# LilyPad_White_5pcs_v02.net
KiCad netlist of a schematic drawn in EAGLE
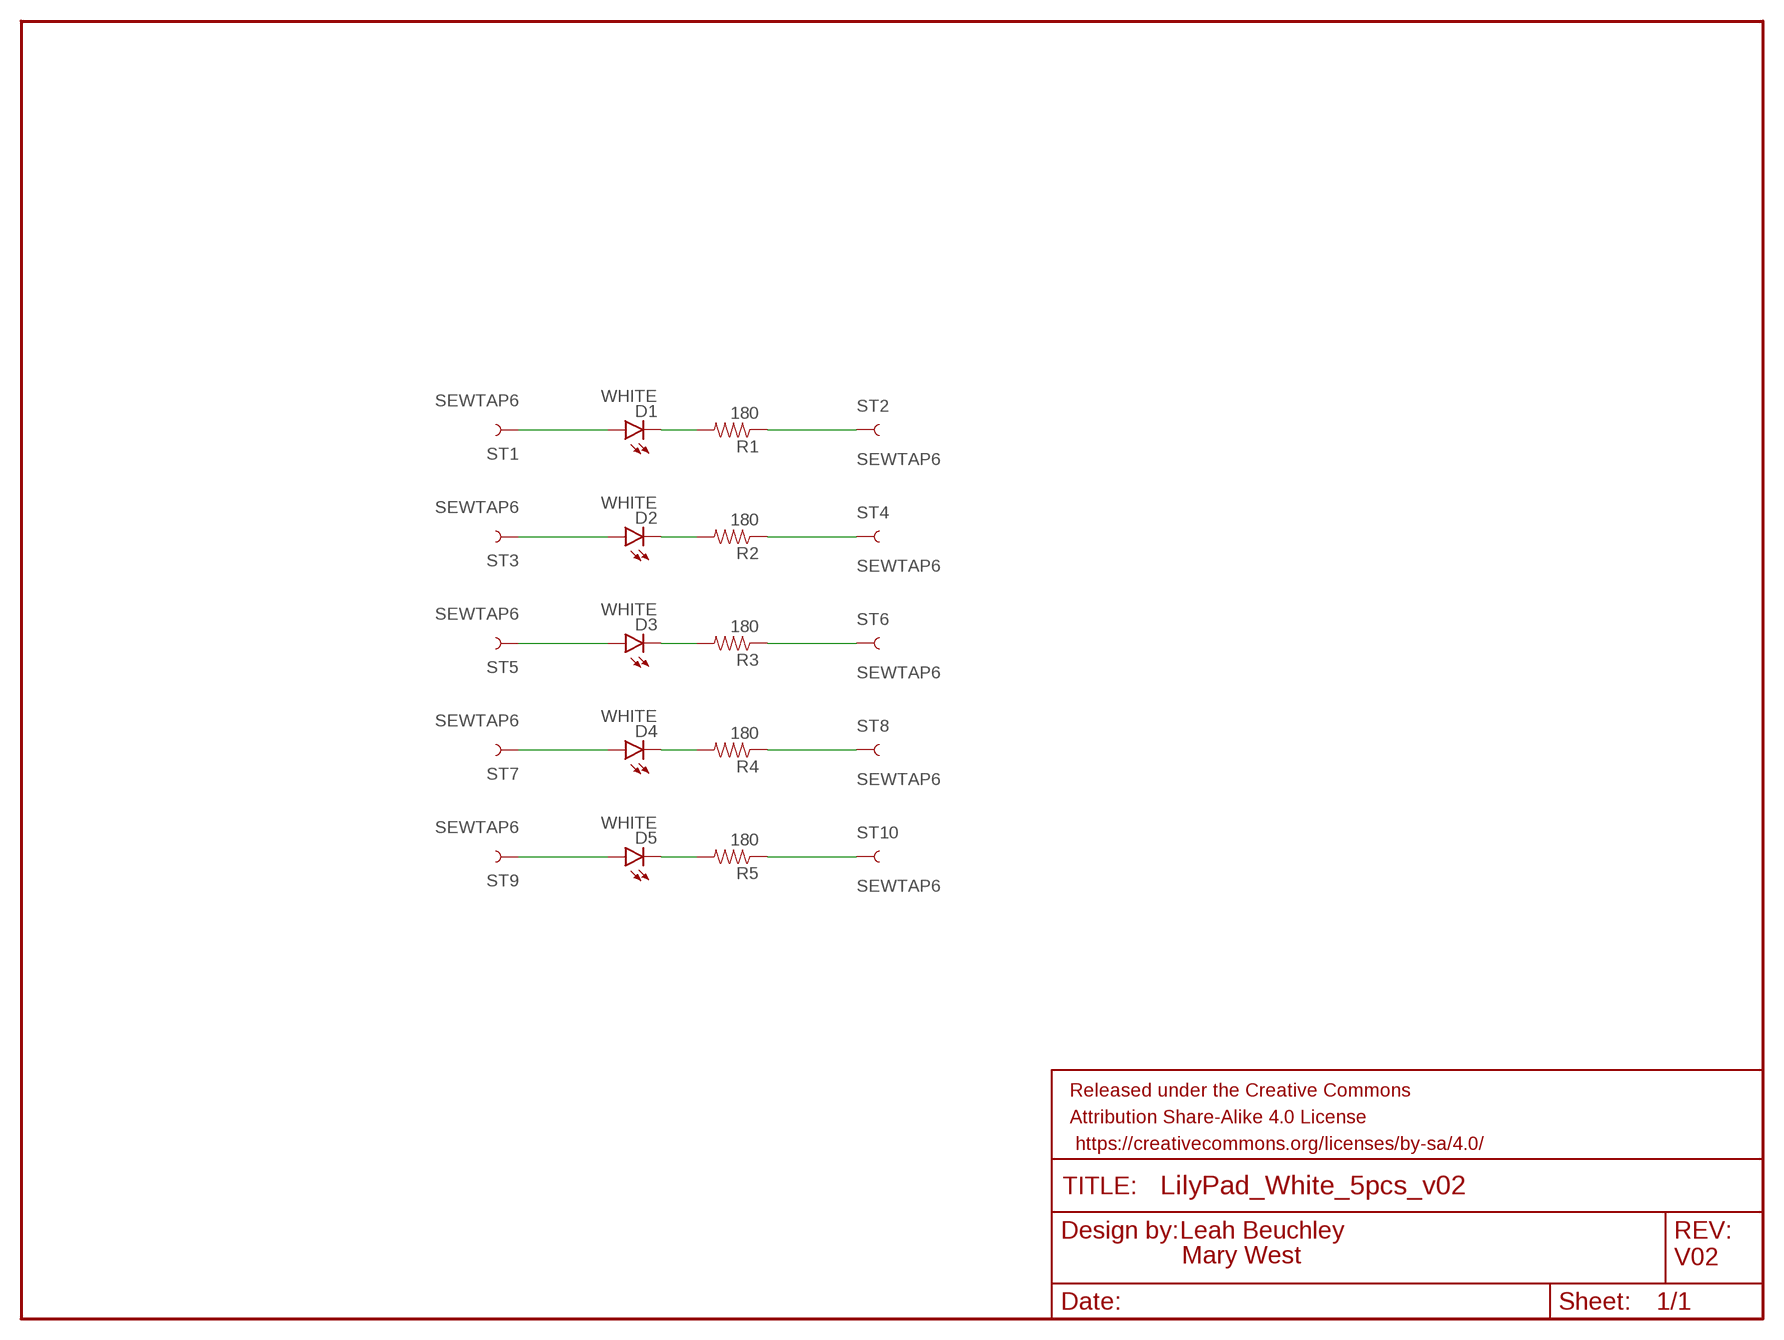
[diagram p0: schematic, sheet 1]

(export (version "E")
  (design (tool "Eeschema 10.0.6"))
  (components
    (comp (ref "D1")
      (value "WHITE")
      (footprint "eagle-import:LED-1206")
      (libsource (lib "eagle-import") (part "LED-WHITE1206"))
    )
    (comp (ref "D2")
      (value "WHITE")
      (footprint "eagle-import:LED-1206")
      (libsource (lib "eagle-import") (part "LED-WHITE1206"))
    )
    (comp (ref "D3")
      (value "WHITE")
      (footprint "eagle-import:LED-1206")
      (libsource (lib "eagle-import") (part "LED-WHITE1206"))
    )
    (comp (ref "D4")
      (value "WHITE")
      (footprint "eagle-import:LED-1206")
      (libsource (lib "eagle-import") (part "LED-WHITE1206"))
    )
    (comp (ref "D5")
      (value "WHITE")
      (footprint "eagle-import:LED-1206")
      (libsource (lib "eagle-import") (part "LED-WHITE1206"))
    )
    (comp (ref "FRAME1")
      (value "FRAME-LETTER")
      (footprint "eagle-import:CREATIVE_COMMONS")
      (libsource (lib "eagle-import") (part "FRAME-LETTER"))
    )
    (comp (ref "R1")
      (value "180")
      (footprint "eagle-import:0603-RES")
      (libsource (lib "eagle-import") (part "180OHM1/10W1%(0603)"))
    )
    (comp (ref "R2")
      (value "180")
      (footprint "eagle-import:0603-RES")
      (libsource (lib "eagle-import") (part "180OHM1/10W1%(0603)"))
    )
    (comp (ref "R3")
      (value "180")
      (footprint "eagle-import:0603-RES")
      (libsource (lib "eagle-import") (part "180OHM1/10W1%(0603)"))
    )
    (comp (ref "R4")
      (value "180")
      (footprint "eagle-import:0603-RES")
      (libsource (lib "eagle-import") (part "180OHM1/10W1%(0603)"))
    )
    (comp (ref "R5")
      (value "180")
      (footprint "eagle-import:0603-RES")
      (libsource (lib "eagle-import") (part "180OHM1/10W1%(0603)"))
    )
    (comp (ref "ST1")
      (value "SEWTAP6")
      (footprint "eagle-import:PETAL-SMALL-2SIDE")
      (libsource (lib "eagle-import") (part "SEWTAP6"))
    )
    (comp (ref "ST2")
      (value "SEWTAP6")
      (footprint "eagle-import:PETAL-SMALL-2SIDE")
      (libsource (lib "eagle-import") (part "SEWTAP6"))
    )
    (comp (ref "ST3")
      (value "SEWTAP6")
      (footprint "eagle-import:PETAL-SMALL-2SIDE")
      (libsource (lib "eagle-import") (part "SEWTAP6"))
    )
    (comp (ref "ST4")
      (value "SEWTAP6")
      (footprint "eagle-import:PETAL-SMALL-2SIDE")
      (libsource (lib "eagle-import") (part "SEWTAP6"))
    )
    (comp (ref "ST5")
      (value "SEWTAP6")
      (footprint "eagle-import:PETAL-SMALL-2SIDE")
      (libsource (lib "eagle-import") (part "SEWTAP6"))
    )
    (comp (ref "ST6")
      (value "SEWTAP6")
      (footprint "eagle-import:PETAL-SMALL-2SIDE")
      (libsource (lib "eagle-import") (part "SEWTAP6"))
    )
    (comp (ref "ST7")
      (value "SEWTAP6")
      (footprint "eagle-import:PETAL-SMALL-2SIDE")
      (libsource (lib "eagle-import") (part "SEWTAP6"))
    )
    (comp (ref "ST8")
      (value "SEWTAP6")
      (footprint "eagle-import:PETAL-SMALL-2SIDE")
      (libsource (lib "eagle-import") (part "SEWTAP6"))
    )
    (comp (ref "ST9")
      (value "SEWTAP6")
      (footprint "eagle-import:PETAL-SMALL-2SIDE")
      (libsource (lib "eagle-import") (part "SEWTAP6"))
    )
    (comp (ref "ST10")
      (value "SEWTAP6")
      (footprint "eagle-import:PETAL-SMALL-2SIDE")
      (libsource (lib "eagle-import") (part "SEWTAP6"))
    )
  )
  (nets
    (net (code "1") (name "Net-(D1-PadA)") (class "Default")
      (node (ref "D1") (pin "A") (pinfunction "A_A") (pintype "passive"))
      (node (ref "ST1") (pin "1") (pinfunction "1_1") (pintype "bidirectional"))
    )
    (net (code "2") (name "Net-(D1-PadC)") (class "Default")
      (node (ref "D1") (pin "C") (pinfunction "C_C") (pintype "passive"))
      (node (ref "R1") (pin "2") (pinfunction "2_2") (pintype "passive"))
    )
    (net (code "3") (name "Net-(D2-PadA)") (class "Default")
      (node (ref "D2") (pin "A") (pinfunction "A_A") (pintype "passive"))
      (node (ref "ST3") (pin "1") (pinfunction "1_1") (pintype "bidirectional"))
    )
    (net (code "4") (name "Net-(D2-PadC)") (class "Default")
      (node (ref "D2") (pin "C") (pinfunction "C_C") (pintype "passive"))
      (node (ref "R2") (pin "2") (pinfunction "2_2") (pintype "passive"))
    )
    (net (code "5") (name "Net-(D3-PadA)") (class "Default")
      (node (ref "D3") (pin "A") (pinfunction "A_A") (pintype "passive"))
      (node (ref "ST5") (pin "1") (pinfunction "1_1") (pintype "bidirectional"))
    )
    (net (code "6") (name "Net-(D3-PadC)") (class "Default")
      (node (ref "D3") (pin "C") (pinfunction "C_C") (pintype "passive"))
      (node (ref "R3") (pin "2") (pinfunction "2_2") (pintype "passive"))
    )
    (net (code "7") (name "Net-(D4-PadA)") (class "Default")
      (node (ref "D4") (pin "A") (pinfunction "A_A") (pintype "passive"))
      (node (ref "ST7") (pin "1") (pinfunction "1_1") (pintype "bidirectional"))
    )
    (net (code "8") (name "Net-(D4-PadC)") (class "Default")
      (node (ref "D4") (pin "C") (pinfunction "C_C") (pintype "passive"))
      (node (ref "R4") (pin "2") (pinfunction "2_2") (pintype "passive"))
    )
    (net (code "9") (name "Net-(D5-PadA)") (class "Default")
      (node (ref "D5") (pin "A") (pinfunction "A_A") (pintype "passive"))
      (node (ref "ST9") (pin "1") (pinfunction "1_1") (pintype "bidirectional"))
    )
    (net (code "10") (name "Net-(D5-PadC)") (class "Default")
      (node (ref "D5") (pin "C") (pinfunction "C_C") (pintype "passive"))
      (node (ref "R5") (pin "2") (pinfunction "2_2") (pintype "passive"))
    )
    (net (code "11") (name "Net-(R1-Pad1)") (class "Default")
      (node (ref "R1") (pin "1") (pinfunction "1_1") (pintype "passive"))
      (node (ref "ST2") (pin "1") (pinfunction "1_1") (pintype "bidirectional"))
    )
    (net (code "12") (name "Net-(R2-Pad1)") (class "Default")
      (node (ref "R2") (pin "1") (pinfunction "1_1") (pintype "passive"))
      (node (ref "ST4") (pin "1") (pinfunction "1_1") (pintype "bidirectional"))
    )
    (net (code "13") (name "Net-(R3-Pad1)") (class "Default")
      (node (ref "R3") (pin "1") (pinfunction "1_1") (pintype "passive"))
      (node (ref "ST6") (pin "1") (pinfunction "1_1") (pintype "bidirectional"))
    )
    (net (code "14") (name "Net-(R4-Pad1)") (class "Default")
      (node (ref "R4") (pin "1") (pinfunction "1_1") (pintype "passive"))
      (node (ref "ST8") (pin "1") (pinfunction "1_1") (pintype "bidirectional"))
    )
    (net (code "15") (name "Net-(R5-Pad1)") (class "Default")
      (node (ref "R5") (pin "1") (pinfunction "1_1") (pintype "passive"))
      (node (ref "ST10") (pin "1") (pinfunction "1_1") (pintype "bidirectional"))
    )
  )
)
